# barGraph.net
KiCad netlist of a schematic drawn in Altium Designer
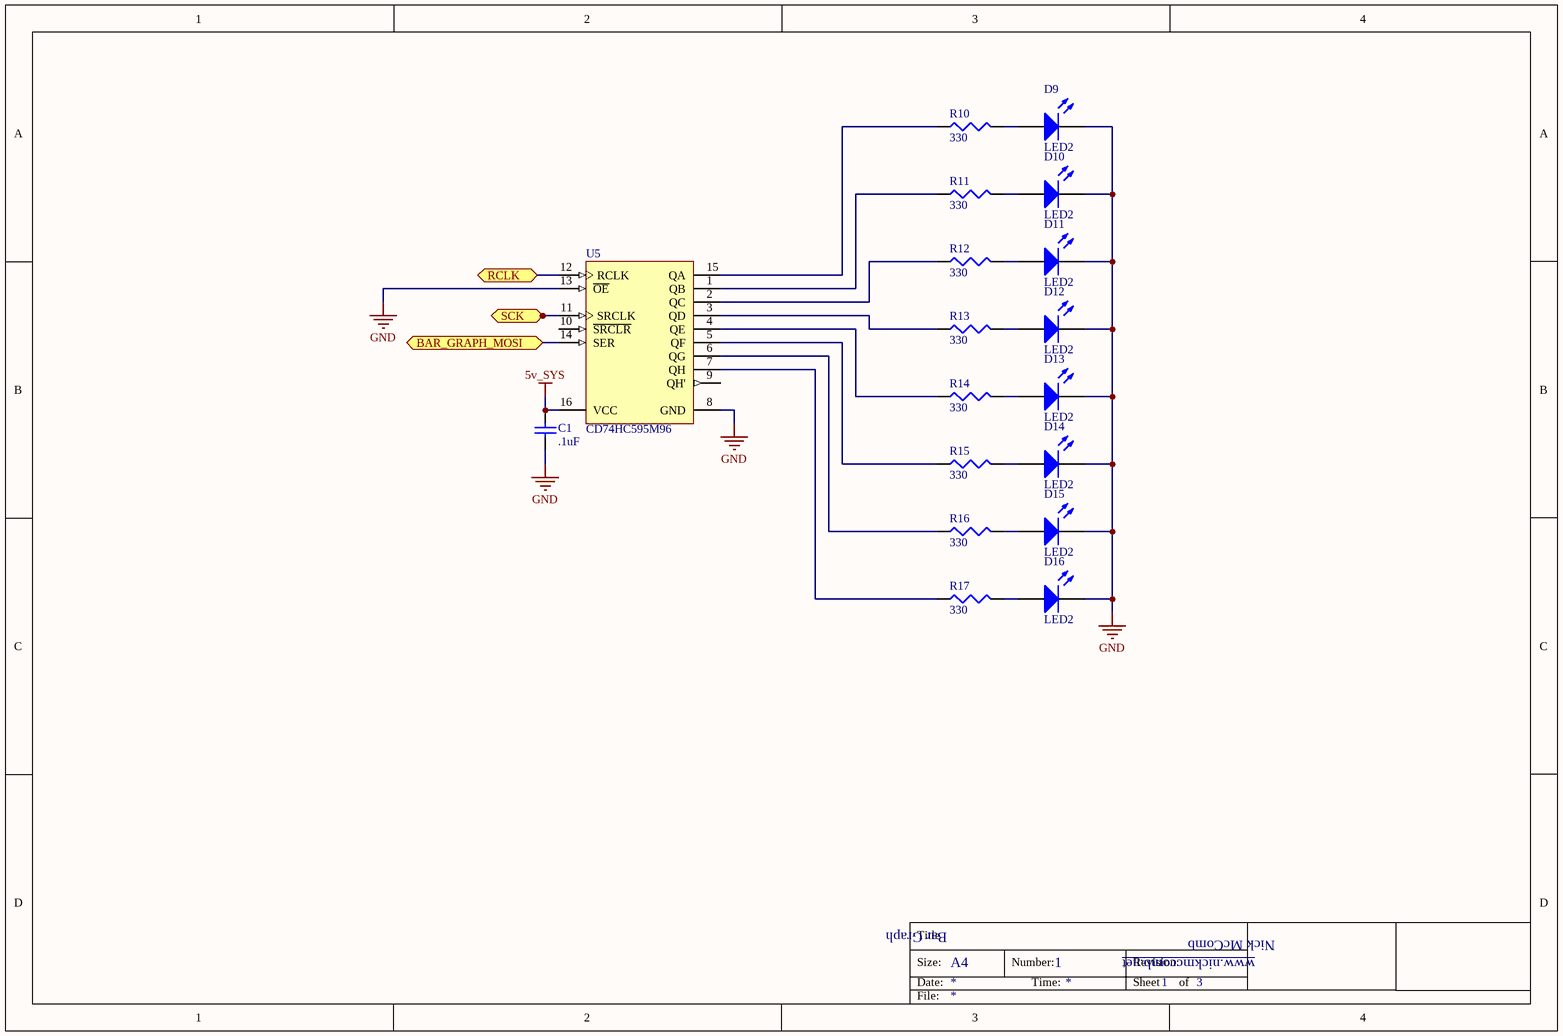
[diagram p0: barGraph.SchDoc]

(export (version "E")
  (design (tool "Eeschema 10.0.6"))
  (components
    (comp (ref "C1")
      (value ".1uF")
      (footprint "C0805")
      (description "Capacitor")
      (fields (field (name "Comment") "0805 style, by default") (field (name "PUBLISHER") "Altium Limited"))
      (libsource (lib "lab2") (part "Cap"))
    )
    (comp (ref "D9")
      (value "LED2")
      (footprint "basic_led")
      (description "Typical RED, GREEN, YELLOW, AMBER GaAs LED")
      (fields (field (name "PUBLISHER") "Altium Limited"))
      (libsource (lib "lab2") (part "LED2"))
    )
    (comp (ref "D10")
      (value "LED2")
      (footprint "basic_led")
      (description "Typical RED, GREEN, YELLOW, AMBER GaAs LED")
      (fields (field (name "PUBLISHER") "Altium Limited"))
      (libsource (lib "lab2") (part "LED2"))
    )
    (comp (ref "D11")
      (value "LED2")
      (footprint "basic_led")
      (description "Typical RED, GREEN, YELLOW, AMBER GaAs LED")
      (fields (field (name "PUBLISHER") "Altium Limited"))
      (libsource (lib "lab2") (part "LED2"))
    )
    (comp (ref "D12")
      (value "LED2")
      (footprint "basic_led")
      (description "Typical RED, GREEN, YELLOW, AMBER GaAs LED")
      (fields (field (name "PUBLISHER") "Altium Limited"))
      (libsource (lib "lab2") (part "LED2"))
    )
    (comp (ref "D13")
      (value "LED2")
      (footprint "basic_led")
      (description "Typical RED, GREEN, YELLOW, AMBER GaAs LED")
      (fields (field (name "PUBLISHER") "Altium Limited"))
      (libsource (lib "lab2") (part "LED2"))
    )
    (comp (ref "D14")
      (value "LED2")
      (footprint "basic_led")
      (description "Typical RED, GREEN, YELLOW, AMBER GaAs LED")
      (fields (field (name "PUBLISHER") "Altium Limited"))
      (libsource (lib "lab2") (part "LED2"))
    )
    (comp (ref "D15")
      (value "LED2")
      (footprint "basic_led")
      (description "Typical RED, GREEN, YELLOW, AMBER GaAs LED")
      (fields (field (name "PUBLISHER") "Altium Limited"))
      (libsource (lib "lab2") (part "LED2"))
    )
    (comp (ref "D16")
      (value "LED2")
      (footprint "basic_led")
      (description "Typical RED, GREEN, YELLOW, AMBER GaAs LED")
      (fields (field (name "PUBLISHER") "Altium Limited"))
      (libsource (lib "lab2") (part "LED2"))
    )
    (comp (ref "R10")
      (value "330")
      (footprint "J1-0603")
      (description "Resistor")
      (fields (field (name "PUBLISHER") "Altium Limited"))
      (libsource (lib "lab2") (part "Res3"))
    )
    (comp (ref "R11")
      (value "330")
      (footprint "J1-0603")
      (description "Resistor")
      (fields (field (name "PUBLISHER") "Altium Limited"))
      (libsource (lib "lab2") (part "Res3"))
    )
    (comp (ref "R12")
      (value "330")
      (footprint "J1-0603")
      (description "Resistor")
      (fields (field (name "PUBLISHER") "Altium Limited"))
      (libsource (lib "lab2") (part "Res3"))
    )
    (comp (ref "R13")
      (value "330")
      (footprint "J1-0603")
      (description "Resistor")
      (fields (field (name "PUBLISHER") "Altium Limited"))
      (libsource (lib "lab2") (part "Res3"))
    )
    (comp (ref "R14")
      (value "330")
      (footprint "J1-0603")
      (description "Resistor")
      (fields (field (name "PUBLISHER") "Altium Limited"))
      (libsource (lib "lab2") (part "Res3"))
    )
    (comp (ref "R15")
      (value "330")
      (footprint "J1-0603")
      (description "Resistor")
      (fields (field (name "PUBLISHER") "Altium Limited"))
      (libsource (lib "lab2") (part "Res3"))
    )
    (comp (ref "R16")
      (value "330")
      (footprint "J1-0603")
      (description "Resistor")
      (fields (field (name "PUBLISHER") "Altium Limited"))
      (libsource (lib "lab2") (part "Res3"))
    )
    (comp (ref "R17")
      (value "330")
      (footprint "J1-0603")
      (description "Resistor")
      (fields (field (name "PUBLISHER") "Altium Limited"))
      (libsource (lib "lab2") (part "Res3"))
    )
    (comp (ref "U5")
      (value "CD74HC595M96")
      (footprint "D0016A_L")
      (description "8-Bit Shift Registers With 3-State Output Registers, D0016A, LARGE T&R")
      (fields (field (name "PART NUMBER") "CD74HC595"))
      (libsource (lib "Altium Content Vault") (part "TI-CD74HC595-16"))
    )
  )
  (nets
    (net (code "1") (name "/BAR_GRAPH_MOSI") (class "Default")
      (node (ref "U5") (pin "14") (pinfunction "SER_14") (pintype "input"))
    )
    (net (code "2") (name "/RCLK") (class "Default")
      (node (ref "U5") (pin "12") (pinfunction "RCLK_12") (pintype "input"))
    )
    (net (code "3") (name "/SCK") (class "Default")
      (node (ref "U5") (pin "11") (pinfunction "SRCLK_11") (pintype "input"))
    )
    (net (code "4") (name "5v_SYS") (class "Default")
      (node (ref "C1") (pin "2") (pinfunction "2_2") (pintype "passive"))
      (node (ref "U5") (pin "16") (pinfunction "VCC_16") (pintype "power_in"))
    )
    (net (code "5") (name "GND") (class "Default")
      (node (ref "C1") (pin "1") (pinfunction "1_1") (pintype "passive"))
      (node (ref "D10") (pin "2") (pinfunction "K_2") (pintype "passive"))
      (node (ref "D11") (pin "2") (pinfunction "K_2") (pintype "passive"))
      (node (ref "D12") (pin "2") (pinfunction "K_2") (pintype "passive"))
      (node (ref "D13") (pin "2") (pinfunction "K_2") (pintype "passive"))
      (node (ref "D14") (pin "2") (pinfunction "K_2") (pintype "passive"))
      (node (ref "D15") (pin "2") (pinfunction "K_2") (pintype "passive"))
      (node (ref "D16") (pin "2") (pinfunction "K_2") (pintype "passive"))
      (node (ref "D9") (pin "2") (pinfunction "K_2") (pintype "passive"))
      (node (ref "U5") (pin "13") (pinfunction "~{OE}_13") (pintype "input"))
      (node (ref "U5") (pin "8") (pinfunction "GND_8") (pintype "power_in"))
    )
    (net (code "6") (name "Net-(D9-A)") (class "Default")
      (node (ref "D9") (pin "1") (pinfunction "A_1") (pintype "passive"))
      (node (ref "R10") (pin "2") (pinfunction "2_2") (pintype "passive"))
    )
    (net (code "7") (name "Net-(D10-A)") (class "Default")
      (node (ref "D10") (pin "1") (pinfunction "A_1") (pintype "passive"))
      (node (ref "R11") (pin "2") (pinfunction "2_2") (pintype "passive"))
    )
    (net (code "8") (name "Net-(D11-A)") (class "Default")
      (node (ref "D11") (pin "1") (pinfunction "A_1") (pintype "passive"))
      (node (ref "R12") (pin "2") (pinfunction "2_2") (pintype "passive"))
    )
    (net (code "9") (name "Net-(D12-A)") (class "Default")
      (node (ref "D12") (pin "1") (pinfunction "A_1") (pintype "passive"))
      (node (ref "R13") (pin "2") (pinfunction "2_2") (pintype "passive"))
    )
    (net (code "10") (name "Net-(D13-A)") (class "Default")
      (node (ref "D13") (pin "1") (pinfunction "A_1") (pintype "passive"))
      (node (ref "R14") (pin "2") (pinfunction "2_2") (pintype "passive"))
    )
    (net (code "11") (name "Net-(D14-A)") (class "Default")
      (node (ref "D14") (pin "1") (pinfunction "A_1") (pintype "passive"))
      (node (ref "R15") (pin "2") (pinfunction "2_2") (pintype "passive"))
    )
    (net (code "12") (name "Net-(D15-A)") (class "Default")
      (node (ref "D15") (pin "1") (pinfunction "A_1") (pintype "passive"))
      (node (ref "R16") (pin "2") (pinfunction "2_2") (pintype "passive"))
    )
    (net (code "13") (name "Net-(D16-A)") (class "Default")
      (node (ref "D16") (pin "1") (pinfunction "A_1") (pintype "passive"))
      (node (ref "R17") (pin "2") (pinfunction "2_2") (pintype "passive"))
    )
    (net (code "14") (name "Net-(U5-QA)") (class "Default")
      (node (ref "R10") (pin "1") (pinfunction "1_1") (pintype "passive"))
      (node (ref "U5") (pin "15") (pinfunction "QA_15") (pintype "tri_state"))
    )
    (net (code "15") (name "Net-(U5-QB)") (class "Default")
      (node (ref "R11") (pin "1") (pinfunction "1_1") (pintype "passive"))
      (node (ref "U5") (pin "1") (pinfunction "QB_1") (pintype "tri_state"))
    )
    (net (code "16") (name "Net-(U5-QC)") (class "Default")
      (node (ref "R12") (pin "1") (pinfunction "1_1") (pintype "passive"))
      (node (ref "U5") (pin "2") (pinfunction "QC_2") (pintype "tri_state"))
    )
    (net (code "17") (name "Net-(U5-QD)") (class "Default")
      (node (ref "R13") (pin "1") (pinfunction "1_1") (pintype "passive"))
      (node (ref "U5") (pin "3") (pinfunction "QD_3") (pintype "tri_state"))
    )
    (net (code "18") (name "Net-(U5-QE)") (class "Default")
      (node (ref "R14") (pin "1") (pinfunction "1_1") (pintype "passive"))
      (node (ref "U5") (pin "4") (pinfunction "QE_4") (pintype "tri_state"))
    )
    (net (code "19") (name "Net-(U5-QF)") (class "Default")
      (node (ref "R15") (pin "1") (pinfunction "1_1") (pintype "passive"))
      (node (ref "U5") (pin "5") (pinfunction "QF_5") (pintype "tri_state"))
    )
    (net (code "20") (name "Net-(U5-QG)") (class "Default")
      (node (ref "R16") (pin "1") (pinfunction "1_1") (pintype "passive"))
      (node (ref "U5") (pin "6") (pinfunction "QG_6") (pintype "tri_state"))
    )
    (net (code "21") (name "Net-(U5-QH)") (class "Default")
      (node (ref "R17") (pin "1") (pinfunction "1_1") (pintype "passive"))
      (node (ref "U5") (pin "7") (pinfunction "QH_7") (pintype "tri_state"))
    )
    (net (code "22") (name "unconnected-(U5-QH'-Pad9)") (class "Default")
      (node (ref "U5") (pin "9") (pinfunction "QH'_9") (pintype "output"))
    )
    (net (code "23") (name "unconnected-(U5-~{SRCLR}-Pad10)") (class "Default")
      (node (ref "U5") (pin "10") (pinfunction "~{SRCLR}_10") (pintype "input"))
    )
  )
)
